# B683C.net
KiCad netlist of a schematic drawn in EAGLE
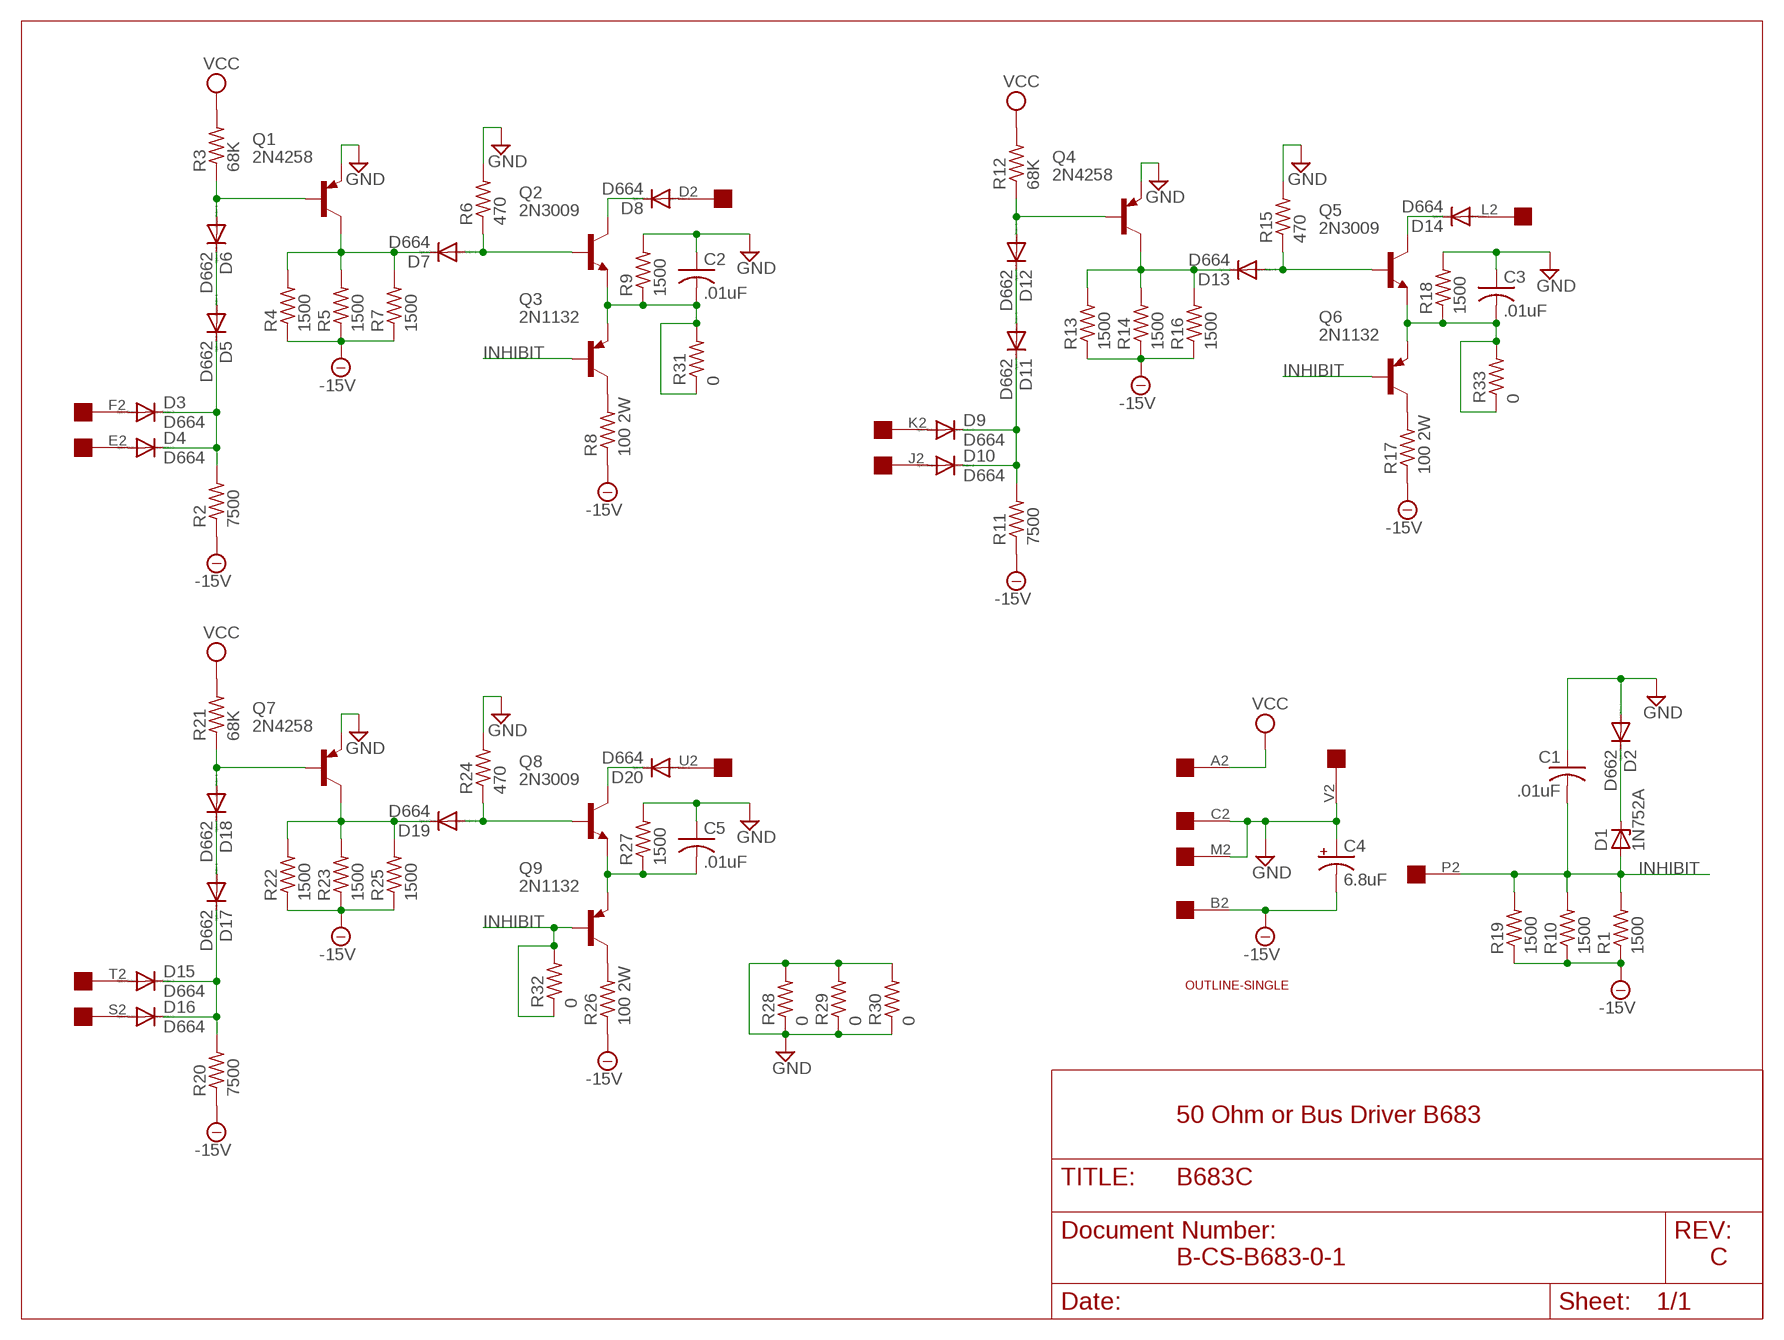
[diagram p0: schematic, sheet 1]

(export (version "E")
  (design (tool "Eeschema 10.0.6"))
  (components
    (comp (ref "C1")
      (value ".01uF")
      (footprint "eagle-import:C063-025X075")
      (libsource (lib "eagle-import") (part "C-US"))
    )
    (comp (ref "C2")
      (value ".01uF")
      (footprint "eagle-import:C063-025X075")
      (libsource (lib "eagle-import") (part "C-US"))
    )
    (comp (ref "C3")
      (value ".01uF")
      (footprint "eagle-import:C063-025X075")
      (libsource (lib "eagle-import") (part "C-US"))
    )
    (comp (ref "C4")
      (value "6.8uF")
      (footprint "eagle-import:E12-8")
      (libsource (lib "eagle-import") (part "CPOL-USE20-8AXIAL"))
    )
    (comp (ref "C5")
      (value ".01uF")
      (footprint "eagle-import:C063-025X075")
      (libsource (lib "eagle-import") (part "C-US"))
    )
    (comp (ref "D1")
      (value "1N752A")
      (footprint "eagle-import:DO35Z10")
      (libsource (lib "eagle-import") (part "ZENER-DIODEDO35Z10"))
    )
    (comp (ref "D2")
      (value "D662")
      (footprint "eagle-import:DO35-10")
      (libsource (lib "eagle-import") (part "DIODE-DO35-10"))
    )
    (comp (ref "D3")
      (value "D664")
      (footprint "eagle-import:DO35-10")
      (libsource (lib "eagle-import") (part "DIODE-DO35-10"))
    )
    (comp (ref "D4")
      (value "D664")
      (footprint "eagle-import:DO35-10")
      (libsource (lib "eagle-import") (part "DIODE-DO35-10"))
    )
    (comp (ref "D5")
      (value "D662")
      (footprint "eagle-import:DO35-10")
      (libsource (lib "eagle-import") (part "DIODE-DO35-10"))
    )
    (comp (ref "D6")
      (value "D662")
      (footprint "eagle-import:DO35-10")
      (libsource (lib "eagle-import") (part "DIODE-DO35-10"))
    )
    (comp (ref "D7")
      (value "D664")
      (footprint "eagle-import:DO35-10")
      (libsource (lib "eagle-import") (part "DIODE-DO35-10"))
    )
    (comp (ref "D8")
      (value "D664")
      (footprint "eagle-import:DO35-10")
      (libsource (lib "eagle-import") (part "DIODE-DO35-10"))
    )
    (comp (ref "D9")
      (value "D664")
      (footprint "eagle-import:DO35-10")
      (libsource (lib "eagle-import") (part "DIODE-DO35-10"))
    )
    (comp (ref "D10")
      (value "D664")
      (footprint "eagle-import:DO35-10")
      (libsource (lib "eagle-import") (part "DIODE-DO35-10"))
    )
    (comp (ref "D11")
      (value "D662")
      (footprint "eagle-import:DO35-10")
      (libsource (lib "eagle-import") (part "DIODE-DO35-10"))
    )
    (comp (ref "D12")
      (value "D662")
      (footprint "eagle-import:DO35-10")
      (libsource (lib "eagle-import") (part "DIODE-DO35-10"))
    )
    (comp (ref "D13")
      (value "D664")
      (footprint "eagle-import:DO35-10")
      (libsource (lib "eagle-import") (part "DIODE-DO35-10"))
    )
    (comp (ref "D14")
      (value "D664")
      (footprint "eagle-import:DO35-10")
      (libsource (lib "eagle-import") (part "DIODE-DO35-10"))
    )
    (comp (ref "D15")
      (value "D664")
      (footprint "eagle-import:DO35-10")
      (libsource (lib "eagle-import") (part "DIODE-DO35-10"))
    )
    (comp (ref "D16")
      (value "D664")
      (footprint "eagle-import:DO35-10")
      (libsource (lib "eagle-import") (part "DIODE-DO35-10"))
    )
    (comp (ref "D17")
      (value "D662")
      (footprint "eagle-import:DO35-10")
      (libsource (lib "eagle-import") (part "DIODE-DO35-10"))
    )
    (comp (ref "D18")
      (value "D662")
      (footprint "eagle-import:DO35-10")
      (libsource (lib "eagle-import") (part "DIODE-DO35-10"))
    )
    (comp (ref "D19")
      (value "D664")
      (footprint "eagle-import:DO35-10")
      (libsource (lib "eagle-import") (part "DIODE-DO35-10"))
    )
    (comp (ref "D20")
      (value "D664")
      (footprint "eagle-import:DO35-10")
      (libsource (lib "eagle-import") (part "DIODE-DO35-10"))
    )
    (comp (ref "Q1")
      (value "2N4258")
      (footprint "eagle-import:TO5")
      (libsource (lib "eagle-import") (part "-PNP-TO5"))
    )
    (comp (ref "Q2")
      (value "2N3009")
      (footprint "eagle-import:TO5")
      (libsource (lib "eagle-import") (part "-NPN-TO5"))
    )
    (comp (ref "Q3")
      (value "2N1132")
      (footprint "eagle-import:TO5")
      (libsource (lib "eagle-import") (part "-PNP-TO5"))
    )
    (comp (ref "Q4")
      (value "2N4258")
      (footprint "eagle-import:TO5")
      (libsource (lib "eagle-import") (part "-PNP-TO5"))
    )
    (comp (ref "Q5")
      (value "2N3009")
      (footprint "eagle-import:TO5")
      (libsource (lib "eagle-import") (part "-NPN-TO5"))
    )
    (comp (ref "Q6")
      (value "2N1132")
      (footprint "eagle-import:TO5")
      (libsource (lib "eagle-import") (part "-PNP-TO5"))
    )
    (comp (ref "Q7")
      (value "2N4258")
      (footprint "eagle-import:TO5")
      (libsource (lib "eagle-import") (part "-PNP-TO5"))
    )
    (comp (ref "Q8")
      (value "2N3009")
      (footprint "eagle-import:TO5")
      (libsource (lib "eagle-import") (part "-NPN-TO5"))
    )
    (comp (ref "Q9")
      (value "2N1132")
      (footprint "eagle-import:TO5")
      (libsource (lib "eagle-import") (part "-PNP-TO5"))
    )
    (comp (ref "R1")
      (value "1500")
      (footprint "eagle-import:0207_10")
      (libsource (lib "eagle-import") (part "R-US_0207/10"))
    )
    (comp (ref "R2")
      (value "7500")
      (footprint "eagle-import:0207_10")
      (libsource (lib "eagle-import") (part "R-US_0207/10"))
    )
    (comp (ref "R3")
      (value "68K")
      (footprint "eagle-import:0207_10")
      (libsource (lib "eagle-import") (part "R-US_0207/10"))
    )
    (comp (ref "R4")
      (value "1500")
      (footprint "eagle-import:0207_10")
      (libsource (lib "eagle-import") (part "R-US_0207/10"))
    )
    (comp (ref "R5")
      (value "1500")
      (footprint "eagle-import:0207_10")
      (libsource (lib "eagle-import") (part "R-US_0207/10"))
    )
    (comp (ref "R6")
      (value "470")
      (footprint "eagle-import:0207_10")
      (libsource (lib "eagle-import") (part "R-US_0207/10"))
    )
    (comp (ref "R7")
      (value "1500")
      (footprint "eagle-import:0207_10")
      (libsource (lib "eagle-import") (part "R-US_0207/10"))
    )
    (comp (ref "R8")
      (value "100 2W")
      (footprint "eagle-import:0818_25")
      (libsource (lib "eagle-import") (part "R-US_0818/25"))
    )
    (comp (ref "R9")
      (value "1500")
      (footprint "eagle-import:0207_10")
      (libsource (lib "eagle-import") (part "R-US_0207/10"))
    )
    (comp (ref "R10")
      (value "1500")
      (footprint "eagle-import:0207_10")
      (libsource (lib "eagle-import") (part "R-US_0207/10"))
    )
    (comp (ref "R11")
      (value "7500")
      (footprint "eagle-import:0207_10")
      (libsource (lib "eagle-import") (part "R-US_0207/10"))
    )
    (comp (ref "R12")
      (value "68K")
      (footprint "eagle-import:0207_10")
      (libsource (lib "eagle-import") (part "R-US_0207/10"))
    )
    (comp (ref "R13")
      (value "1500")
      (footprint "eagle-import:0207_10")
      (libsource (lib "eagle-import") (part "R-US_0207/10"))
    )
    (comp (ref "R14")
      (value "1500")
      (footprint "eagle-import:0207_10")
      (libsource (lib "eagle-import") (part "R-US_0207/10"))
    )
    (comp (ref "R15")
      (value "470")
      (footprint "eagle-import:0207_10")
      (libsource (lib "eagle-import") (part "R-US_0207/10"))
    )
    (comp (ref "R16")
      (value "1500")
      (footprint "eagle-import:0207_10")
      (libsource (lib "eagle-import") (part "R-US_0207/10"))
    )
    (comp (ref "R17")
      (value "100 2W")
      (footprint "eagle-import:0818_25")
      (libsource (lib "eagle-import") (part "R-US_0818/25"))
    )
    (comp (ref "R18")
      (value "1500")
      (footprint "eagle-import:0207_10")
      (libsource (lib "eagle-import") (part "R-US_0207/10"))
    )
    (comp (ref "R19")
      (value "1500")
      (footprint "eagle-import:0207_10")
      (libsource (lib "eagle-import") (part "R-US_0207/10"))
    )
    (comp (ref "R20")
      (value "7500")
      (footprint "eagle-import:0207_10")
      (libsource (lib "eagle-import") (part "R-US_0207/10"))
    )
    (comp (ref "R21")
      (value "68K")
      (footprint "eagle-import:0207_10")
      (libsource (lib "eagle-import") (part "R-US_0207/10"))
    )
    (comp (ref "R22")
      (value "1500")
      (footprint "eagle-import:0207_10")
      (libsource (lib "eagle-import") (part "R-US_0207/10"))
    )
    (comp (ref "R23")
      (value "1500")
      (footprint "eagle-import:0207_10")
      (libsource (lib "eagle-import") (part "R-US_0207/10"))
    )
    (comp (ref "R24")
      (value "470")
      (footprint "eagle-import:0207_10")
      (libsource (lib "eagle-import") (part "R-US_0207/10"))
    )
    (comp (ref "R25")
      (value "1500")
      (footprint "eagle-import:0207_10")
      (libsource (lib "eagle-import") (part "R-US_0207/10"))
    )
    (comp (ref "R26")
      (value "100 2W")
      (footprint "eagle-import:0818_25")
      (libsource (lib "eagle-import") (part "R-US_0818/25"))
    )
    (comp (ref "R27")
      (value "1500")
      (footprint "eagle-import:0207_10")
      (libsource (lib "eagle-import") (part "R-US_0207/10"))
    )
    (comp (ref "R28")
      (value "0")
      (footprint "eagle-import:0207_10")
      (libsource (lib "eagle-import") (part "R-US_0207/10"))
    )
    (comp (ref "R29")
      (value "0")
      (footprint "eagle-import:0207_10")
      (libsource (lib "eagle-import") (part "R-US_0207/10"))
    )
    (comp (ref "R30")
      (value "0")
      (footprint "eagle-import:0207_10")
      (libsource (lib "eagle-import") (part "R-US_0207/10"))
    )
    (comp (ref "R31")
      (value "0")
      (footprint "eagle-import:0207_10")
      (libsource (lib "eagle-import") (part "R-US_0207/10"))
    )
    (comp (ref "R32")
      (value "0")
      (footprint "eagle-import:0207_10")
      (libsource (lib "eagle-import") (part "R-US_0207/10"))
    )
    (comp (ref "R33")
      (value "0")
      (footprint "eagle-import:0207_10")
      (libsource (lib "eagle-import") (part "R-US_0207/10"))
    )
    (comp (ref "U$1")
      (value "OUTLINE-SINGLE")
      (footprint "eagle-import:SINGLE")
      (libsource (lib "eagle-import") (part "OUTLINE-SINGLE"))
    )
    (comp (ref "U$2")
      (value "EDGE-1")
      (footprint "eagle-import:EDGE-CON1")
      (libsource (lib "eagle-import") (part "EDGE-1"))
    )
  )
  (nets
    (net (code "1") (name "-15V") (class "Default")
      (node (ref "C4") (pin "-") (pinfunction "-_-") (pintype "passive"))
      (node (ref "R1") (pin "1") (pinfunction "1_1") (pintype "passive"))
      (node (ref "R10") (pin "1") (pinfunction "1_1") (pintype "passive"))
      (node (ref "R11") (pin "1") (pinfunction "1_1") (pintype "passive"))
      (node (ref "R13") (pin "1") (pinfunction "1_1") (pintype "passive"))
      (node (ref "R14") (pin "1") (pinfunction "1_1") (pintype "passive"))
      (node (ref "R16") (pin "1") (pinfunction "1_1") (pintype "passive"))
      (node (ref "R17") (pin "1") (pinfunction "1_1") (pintype "passive"))
      (node (ref "R19") (pin "1") (pinfunction "1_1") (pintype "passive"))
      (node (ref "R2") (pin "1") (pinfunction "1_1") (pintype "passive"))
      (node (ref "R20") (pin "1") (pinfunction "1_1") (pintype "passive"))
      (node (ref "R22") (pin "1") (pinfunction "1_1") (pintype "passive"))
      (node (ref "R23") (pin "1") (pinfunction "1_1") (pintype "passive"))
      (node (ref "R25") (pin "1") (pinfunction "1_1") (pintype "passive"))
      (node (ref "R26") (pin "1") (pinfunction "1_1") (pintype "passive"))
      (node (ref "R4") (pin "1") (pinfunction "1_1") (pintype "passive"))
      (node (ref "R5") (pin "1") (pinfunction "1_1") (pintype "passive"))
      (node (ref "R7") (pin "1") (pinfunction "1_1") (pintype "passive"))
      (node (ref "R8") (pin "1") (pinfunction "1_1") (pintype "passive"))
      (node (ref "U$2") (pin "B2") (pinfunction "1_B2") (pintype "bidirectional"))
    )
    (net (code "2") (name "/INHIBIT") (class "Default")
      (node (ref "C1") (pin "2") (pinfunction "2_2") (pintype "passive"))
      (node (ref "D1") (pin "A") (pinfunction "A_A") (pintype "passive"))
      (node (ref "Q3") (pin "2") (pinfunction "B_2") (pintype "passive"))
      (node (ref "Q6") (pin "2") (pinfunction "B_2") (pintype "passive"))
      (node (ref "Q9") (pin "2") (pinfunction "B_2") (pintype "passive"))
      (node (ref "R1") (pin "2") (pinfunction "2_2") (pintype "passive"))
      (node (ref "R10") (pin "2") (pinfunction "2_2") (pintype "passive"))
      (node (ref "R19") (pin "2") (pinfunction "2_2") (pintype "passive"))
      (node (ref "R32") (pin "1") (pinfunction "1_1") (pintype "passive"))
      (node (ref "R32") (pin "2") (pinfunction "2_2") (pintype "passive"))
      (node (ref "U$2") (pin "P2") (pinfunction "1_P2") (pintype "bidirectional"))
    )
    (net (code "3") (name "GND") (class "Default")
      (node (ref "C1") (pin "1") (pinfunction "1_1") (pintype "passive"))
      (node (ref "C2") (pin "1") (pinfunction "1_1") (pintype "passive"))
      (node (ref "C3") (pin "1") (pinfunction "1_1") (pintype "passive"))
      (node (ref "C4") (pin "+") (pinfunction "+_+") (pintype "passive"))
      (node (ref "C5") (pin "1") (pinfunction "1_1") (pintype "passive"))
      (node (ref "D2") (pin "A") (pinfunction "A_A") (pintype "passive"))
      (node (ref "Q1") (pin "1") (pinfunction "E_1") (pintype "passive"))
      (node (ref "Q4") (pin "1") (pinfunction "E_1") (pintype "passive"))
      (node (ref "Q7") (pin "1") (pinfunction "E_1") (pintype "passive"))
      (node (ref "R15") (pin "2") (pinfunction "2_2") (pintype "passive"))
      (node (ref "R18") (pin "2") (pinfunction "2_2") (pintype "passive"))
      (node (ref "R24") (pin "2") (pinfunction "2_2") (pintype "passive"))
      (node (ref "R27") (pin "2") (pinfunction "2_2") (pintype "passive"))
      (node (ref "R28") (pin "1") (pinfunction "1_1") (pintype "passive"))
      (node (ref "R28") (pin "2") (pinfunction "2_2") (pintype "passive"))
      (node (ref "R29") (pin "1") (pinfunction "1_1") (pintype "passive"))
      (node (ref "R29") (pin "2") (pinfunction "2_2") (pintype "passive"))
      (node (ref "R30") (pin "1") (pinfunction "1_1") (pintype "passive"))
      (node (ref "R30") (pin "2") (pinfunction "2_2") (pintype "passive"))
      (node (ref "R6") (pin "2") (pinfunction "2_2") (pintype "passive"))
      (node (ref "R9") (pin "2") (pinfunction "2_2") (pintype "passive"))
      (node (ref "U$2") (pin "C2") (pinfunction "1_C2") (pintype "bidirectional"))
      (node (ref "U$2") (pin "M2") (pinfunction "1_M2") (pintype "bidirectional"))
      (node (ref "U$2") (pin "V2") (pinfunction "1_V2") (pintype "bidirectional"))
    )
    (net (code "4") (name "Net-(D1-PadC)") (class "Default")
      (node (ref "D1") (pin "C") (pinfunction "C_C") (pintype "passive"))
      (node (ref "D2") (pin "C") (pinfunction "C_C") (pintype "passive"))
    )
    (net (code "5") (name "Net-(D3-PadC)") (class "Default")
      (node (ref "D3") (pin "C") (pinfunction "C_C") (pintype "passive"))
      (node (ref "D4") (pin "C") (pinfunction "C_C") (pintype "passive"))
      (node (ref "D5") (pin "C") (pinfunction "C_C") (pintype "passive"))
      (node (ref "R2") (pin "2") (pinfunction "2_2") (pintype "passive"))
    )
    (net (code "6") (name "Net-(D5-PadA)") (class "Default")
      (node (ref "D5") (pin "A") (pinfunction "A_A") (pintype "passive"))
      (node (ref "D6") (pin "C") (pinfunction "C_C") (pintype "passive"))
    )
    (net (code "7") (name "Net-(D10-PadC)") (class "Default")
      (node (ref "D10") (pin "C") (pinfunction "C_C") (pintype "passive"))
      (node (ref "D11") (pin "C") (pinfunction "C_C") (pintype "passive"))
      (node (ref "D9") (pin "C") (pinfunction "C_C") (pintype "passive"))
      (node (ref "R11") (pin "2") (pinfunction "2_2") (pintype "passive"))
    )
    (net (code "8") (name "Net-(D11-PadA)") (class "Default")
      (node (ref "D11") (pin "A") (pinfunction "A_A") (pintype "passive"))
      (node (ref "D12") (pin "C") (pinfunction "C_C") (pintype "passive"))
    )
    (net (code "9") (name "Net-(D15-PadC)") (class "Default")
      (node (ref "D15") (pin "C") (pinfunction "C_C") (pintype "passive"))
      (node (ref "D16") (pin "C") (pinfunction "C_C") (pintype "passive"))
      (node (ref "D17") (pin "C") (pinfunction "C_C") (pintype "passive"))
      (node (ref "R20") (pin "2") (pinfunction "2_2") (pintype "passive"))
    )
    (net (code "10") (name "Net-(D17-PadA)") (class "Default")
      (node (ref "D17") (pin "A") (pinfunction "A_A") (pintype "passive"))
      (node (ref "D18") (pin "C") (pinfunction "C_C") (pintype "passive"))
    )
    (net (code "11") (name "Net-(Q1-B)") (class "Default")
      (node (ref "D6") (pin "A") (pinfunction "A_A") (pintype "passive"))
      (node (ref "Q1") (pin "2") (pinfunction "B_2") (pintype "passive"))
      (node (ref "R3") (pin "1") (pinfunction "1_1") (pintype "passive"))
    )
    (net (code "12") (name "Net-(Q1-C)") (class "Default")
      (node (ref "D7") (pin "C") (pinfunction "C_C") (pintype "passive"))
      (node (ref "Q1") (pin "3") (pinfunction "C_3") (pintype "passive"))
      (node (ref "R4") (pin "2") (pinfunction "2_2") (pintype "passive"))
      (node (ref "R5") (pin "2") (pinfunction "2_2") (pintype "passive"))
      (node (ref "R7") (pin "2") (pinfunction "2_2") (pintype "passive"))
    )
    (net (code "13") (name "Net-(Q2-B)") (class "Default")
      (node (ref "D7") (pin "A") (pinfunction "A_A") (pintype "passive"))
      (node (ref "Q2") (pin "2") (pinfunction "B_2") (pintype "passive"))
      (node (ref "R6") (pin "1") (pinfunction "1_1") (pintype "passive"))
    )
    (net (code "14") (name "Net-(Q2-C)") (class "Default")
      (node (ref "D8") (pin "C") (pinfunction "C_C") (pintype "passive"))
      (node (ref "Q2") (pin "3") (pinfunction "C_3") (pintype "passive"))
    )
    (net (code "15") (name "Net-(Q2-E)") (class "Default")
      (node (ref "C2") (pin "2") (pinfunction "2_2") (pintype "passive"))
      (node (ref "Q2") (pin "1") (pinfunction "E_1") (pintype "passive"))
      (node (ref "Q3") (pin "1") (pinfunction "E_1") (pintype "passive"))
      (node (ref "R31") (pin "1") (pinfunction "1_1") (pintype "passive"))
      (node (ref "R31") (pin "2") (pinfunction "2_2") (pintype "passive"))
      (node (ref "R9") (pin "1") (pinfunction "1_1") (pintype "passive"))
    )
    (net (code "16") (name "Net-(Q3-C)") (class "Default")
      (node (ref "Q3") (pin "3") (pinfunction "C_3") (pintype "passive"))
      (node (ref "R8") (pin "2") (pinfunction "2_2") (pintype "passive"))
    )
    (net (code "17") (name "Net-(Q4-B)") (class "Default")
      (node (ref "D12") (pin "A") (pinfunction "A_A") (pintype "passive"))
      (node (ref "Q4") (pin "2") (pinfunction "B_2") (pintype "passive"))
      (node (ref "R12") (pin "1") (pinfunction "1_1") (pintype "passive"))
    )
    (net (code "18") (name "Net-(Q4-C)") (class "Default")
      (node (ref "D13") (pin "C") (pinfunction "C_C") (pintype "passive"))
      (node (ref "Q4") (pin "3") (pinfunction "C_3") (pintype "passive"))
      (node (ref "R13") (pin "2") (pinfunction "2_2") (pintype "passive"))
      (node (ref "R14") (pin "2") (pinfunction "2_2") (pintype "passive"))
      (node (ref "R16") (pin "2") (pinfunction "2_2") (pintype "passive"))
    )
    (net (code "19") (name "Net-(Q5-B)") (class "Default")
      (node (ref "D13") (pin "A") (pinfunction "A_A") (pintype "passive"))
      (node (ref "Q5") (pin "2") (pinfunction "B_2") (pintype "passive"))
      (node (ref "R15") (pin "1") (pinfunction "1_1") (pintype "passive"))
    )
    (net (code "20") (name "Net-(Q5-C)") (class "Default")
      (node (ref "D14") (pin "C") (pinfunction "C_C") (pintype "passive"))
      (node (ref "Q5") (pin "3") (pinfunction "C_3") (pintype "passive"))
    )
    (net (code "21") (name "Net-(Q5-E)") (class "Default")
      (node (ref "C3") (pin "2") (pinfunction "2_2") (pintype "passive"))
      (node (ref "Q5") (pin "1") (pinfunction "E_1") (pintype "passive"))
      (node (ref "Q6") (pin "1") (pinfunction "E_1") (pintype "passive"))
      (node (ref "R18") (pin "1") (pinfunction "1_1") (pintype "passive"))
      (node (ref "R33") (pin "1") (pinfunction "1_1") (pintype "passive"))
      (node (ref "R33") (pin "2") (pinfunction "2_2") (pintype "passive"))
    )
    (net (code "22") (name "Net-(Q6-C)") (class "Default")
      (node (ref "Q6") (pin "3") (pinfunction "C_3") (pintype "passive"))
      (node (ref "R17") (pin "2") (pinfunction "2_2") (pintype "passive"))
    )
    (net (code "23") (name "Net-(Q7-B)") (class "Default")
      (node (ref "D18") (pin "A") (pinfunction "A_A") (pintype "passive"))
      (node (ref "Q7") (pin "2") (pinfunction "B_2") (pintype "passive"))
      (node (ref "R21") (pin "1") (pinfunction "1_1") (pintype "passive"))
    )
    (net (code "24") (name "Net-(Q7-C)") (class "Default")
      (node (ref "D19") (pin "C") (pinfunction "C_C") (pintype "passive"))
      (node (ref "Q7") (pin "3") (pinfunction "C_3") (pintype "passive"))
      (node (ref "R22") (pin "2") (pinfunction "2_2") (pintype "passive"))
      (node (ref "R23") (pin "2") (pinfunction "2_2") (pintype "passive"))
      (node (ref "R25") (pin "2") (pinfunction "2_2") (pintype "passive"))
    )
    (net (code "25") (name "Net-(Q8-B)") (class "Default")
      (node (ref "D19") (pin "A") (pinfunction "A_A") (pintype "passive"))
      (node (ref "Q8") (pin "2") (pinfunction "B_2") (pintype "passive"))
      (node (ref "R24") (pin "1") (pinfunction "1_1") (pintype "passive"))
    )
    (net (code "26") (name "Net-(Q8-C)") (class "Default")
      (node (ref "D20") (pin "C") (pinfunction "C_C") (pintype "passive"))
      (node (ref "Q8") (pin "3") (pinfunction "C_3") (pintype "passive"))
    )
    (net (code "27") (name "Net-(Q8-E)") (class "Default")
      (node (ref "C5") (pin "2") (pinfunction "2_2") (pintype "passive"))
      (node (ref "Q8") (pin "1") (pinfunction "E_1") (pintype "passive"))
      (node (ref "Q9") (pin "1") (pinfunction "E_1") (pintype "passive"))
      (node (ref "R27") (pin "1") (pinfunction "1_1") (pintype "passive"))
    )
    (net (code "28") (name "Net-(Q9-C)") (class "Default")
      (node (ref "Q9") (pin "3") (pinfunction "C_3") (pintype "passive"))
      (node (ref "R26") (pin "2") (pinfunction "2_2") (pintype "passive"))
    )
    (net (code "29") (name "Net-(U$2D-1)") (class "Default")
      (node (ref "D8") (pin "A") (pinfunction "A_A") (pintype "passive"))
      (node (ref "U$2") (pin "D2") (pinfunction "1_D2") (pintype "bidirectional"))
    )
    (net (code "30") (name "Net-(U$2E-1)") (class "Default")
      (node (ref "D4") (pin "A") (pinfunction "A_A") (pintype "passive"))
      (node (ref "U$2") (pin "E2") (pinfunction "1_E2") (pintype "bidirectional"))
    )
    (net (code "31") (name "Net-(U$2F-1)") (class "Default")
      (node (ref "D3") (pin "A") (pinfunction "A_A") (pintype "passive"))
      (node (ref "U$2") (pin "F2") (pinfunction "1_F2") (pintype "bidirectional"))
    )
    (net (code "32") (name "Net-(U$2H-1)") (class "Default")
      (node (ref "D10") (pin "A") (pinfunction "A_A") (pintype "passive"))
      (node (ref "U$2") (pin "J2") (pinfunction "1_J2") (pintype "bidirectional"))
    )
    (net (code "33") (name "Net-(U$2I-1)") (class "Default")
      (node (ref "D9") (pin "A") (pinfunction "A_A") (pintype "passive"))
      (node (ref "U$2") (pin "K2") (pinfunction "1_K2") (pintype "bidirectional"))
    )
    (net (code "34") (name "Net-(U$2J-1)") (class "Default")
      (node (ref "D14") (pin "A") (pinfunction "A_A") (pintype "passive"))
      (node (ref "U$2") (pin "L2") (pinfunction "1_L2") (pintype "bidirectional"))
    )
    (net (code "35") (name "Net-(U$2O-1)") (class "Default")
      (node (ref "D16") (pin "A") (pinfunction "A_A") (pintype "passive"))
      (node (ref "U$2") (pin "S2") (pinfunction "1_S2") (pintype "bidirectional"))
    )
    (net (code "36") (name "Net-(U$2P-1)") (class "Default")
      (node (ref "D15") (pin "A") (pinfunction "A_A") (pintype "passive"))
      (node (ref "U$2") (pin "T2") (pinfunction "1_T2") (pintype "bidirectional"))
    )
    (net (code "37") (name "Net-(U$2Q-1)") (class "Default")
      (node (ref "D20") (pin "A") (pinfunction "A_A") (pintype "passive"))
      (node (ref "U$2") (pin "U2") (pinfunction "1_U2") (pintype "bidirectional"))
    )
    (net (code "38") (name "VCC") (class "Default")
      (node (ref "R12") (pin "2") (pinfunction "2_2") (pintype "passive"))
      (node (ref "R21") (pin "2") (pinfunction "2_2") (pintype "passive"))
      (node (ref "R3") (pin "2") (pinfunction "2_2") (pintype "passive"))
      (node (ref "U$2") (pin "A2") (pinfunction "1_A2") (pintype "bidirectional"))
    )
  )
)
